# BeagleboneCape.net
KiCad netlist of a schematic drawn in EAGLE
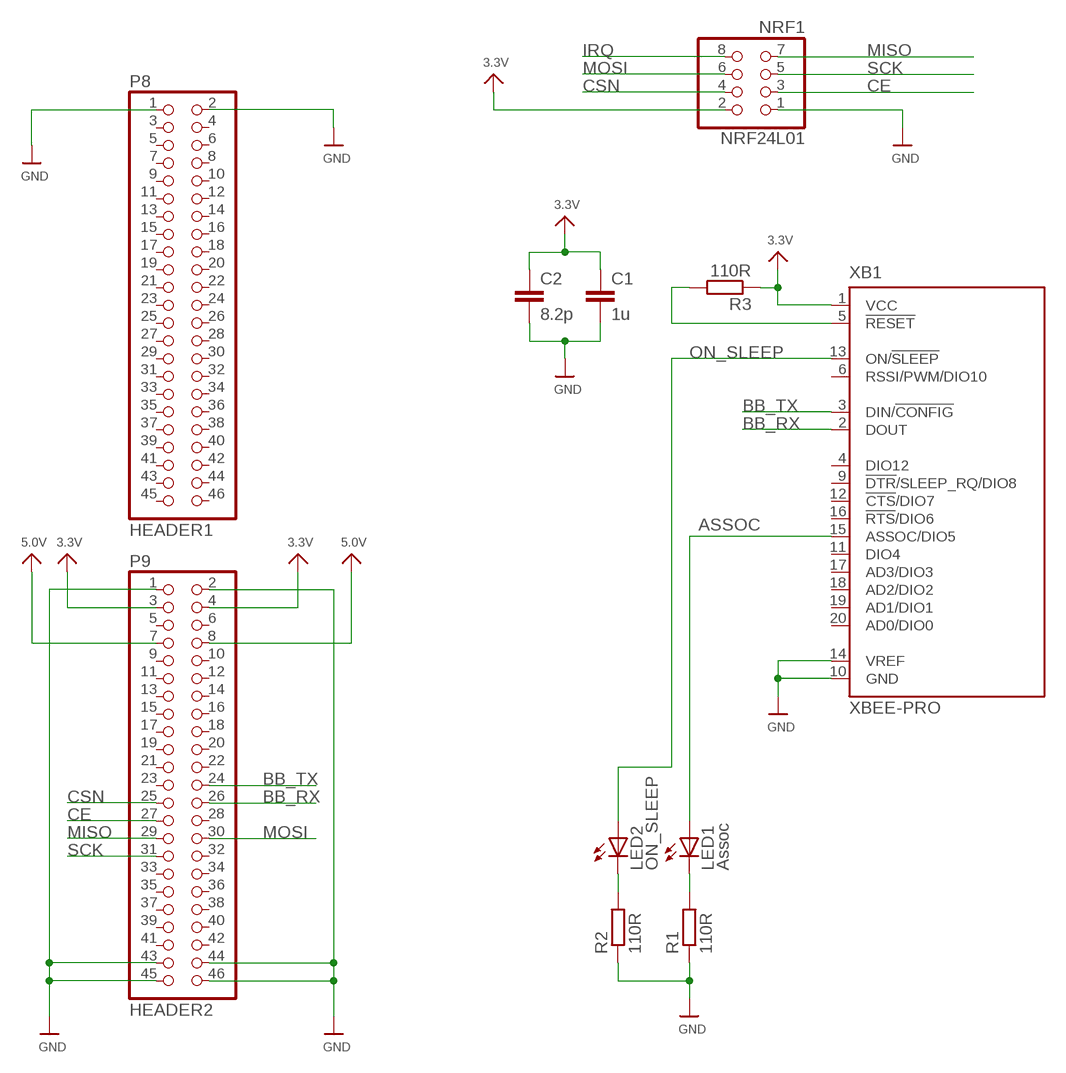
[diagram p0: schematic, sheet 1]

(export (version "E")
  (design (tool "Eeschema 10.0.6"))
  (components
    (comp (ref "C1")
      (value "1u")
      (footprint "eagle-import:C025-025X050")
      (libsource (lib "eagle-import") (part "C-EU025-025X050"))
    )
    (comp (ref "C2")
      (value "8.2p")
      (footprint "eagle-import:C025-025X050")
      (libsource (lib "eagle-import") (part "C-EU025-025X050"))
    )
    (comp (ref "LED1")
      (value "Assoc")
      (footprint "eagle-import:LED5MM")
      (libsource (lib "eagle-import") (part "LED5MM"))
    )
    (comp (ref "LED2")
      (value "ON_SLEEP")
      (footprint "eagle-import:LED5MM")
      (libsource (lib "eagle-import") (part "LED5MM"))
    )
    (comp (ref "NRF24L01")
      (value "NRF1")
      (footprint "eagle-import:2X04")
      (libsource (lib "eagle-import") (part "PINHD-2X4"))
    )
    (comp (ref "P8")
      (value "HEADER1")
      (footprint "eagle-import:2X23")
      (libsource (lib "eagle-import") (part "PINHD-2X24"))
    )
    (comp (ref "P9")
      (value "HEADER2")
      (footprint "eagle-import:2X23")
      (libsource (lib "eagle-import") (part "PINHD-2X24"))
    )
    (comp (ref "R1")
      (value "110R")
      (footprint "eagle-import:0207_7")
      (libsource (lib "eagle-import") (part "R-EU_0207/7"))
    )
    (comp (ref "R2")
      (value "110R")
      (footprint "eagle-import:0207_7")
      (libsource (lib "eagle-import") (part "R-EU_0207/7"))
    )
    (comp (ref "R3")
      (value "110R")
      (footprint "eagle-import:0207_7")
      (libsource (lib "eagle-import") (part "R-EU_0207/7"))
    )
    (comp (ref "XB1")
      (value "XBEE-PRO")
      (footprint "eagle-import:XBEE-PRO")
      (fields (field (name "MPN") "XBP24-AWI-001"))
      (libsource (lib "eagle-import") (part "XBEE-PRO"))
    )
  )
  (nets
    (net (code "1") (name "/ASSOC") (class "Default")
      (node (ref "LED1") (pin "A") (pinfunction "A_A") (pintype "passive"))
      (node (ref "XB1") (pin "15") (pinfunction "ASSOC/DIO5_15") (pintype "bidirectional"))
    )
    (net (code "2") (name "/BB_RX") (class "Default")
      (node (ref "P9") (pin "26") (pinfunction "26_26") (pintype "passive"))
      (node (ref "XB1") (pin "2") (pinfunction "DOUT_2") (pintype "output"))
    )
    (net (code "3") (name "/BB_TX") (class "Default")
      (node (ref "P9") (pin "24") (pinfunction "24_24") (pintype "passive"))
      (node (ref "XB1") (pin "3") (pinfunction "DIN/~{CONFIG}_3") (pintype "input"))
    )
    (net (code "4") (name "/CE") (class "Default")
      (node (ref "NRF24L01") (pin "3") (pinfunction "3_3") (pintype "passive"))
      (node (ref "P9") (pin "27") (pinfunction "27_27") (pintype "passive"))
    )
    (net (code "5") (name "/CSN") (class "Default")
      (node (ref "NRF24L01") (pin "4") (pinfunction "4_4") (pintype "passive"))
      (node (ref "P9") (pin "25") (pinfunction "25_25") (pintype "passive"))
    )
    (net (code "6") (name "/IRQ") (class "Default")
      (node (ref "NRF24L01") (pin "8") (pinfunction "8_8") (pintype "passive"))
    )
    (net (code "7") (name "/MISO") (class "Default")
      (node (ref "NRF24L01") (pin "7") (pinfunction "7_7") (pintype "passive"))
      (node (ref "P9") (pin "29") (pinfunction "29_29") (pintype "passive"))
    )
    (net (code "8") (name "/MOSI") (class "Default")
      (node (ref "NRF24L01") (pin "6") (pinfunction "6_6") (pintype "passive"))
      (node (ref "P9") (pin "30") (pinfunction "30_30") (pintype "passive"))
    )
    (net (code "9") (name "/ON_SLEEP") (class "Default")
      (node (ref "LED2") (pin "A") (pinfunction "A_A") (pintype "passive"))
      (node (ref "XB1") (pin "13") (pinfunction "ON/~{SLEEP}_13") (pintype "output"))
    )
    (net (code "10") (name "/SCK") (class "Default")
      (node (ref "NRF24L01") (pin "5") (pinfunction "5_5") (pintype "passive"))
      (node (ref "P9") (pin "31") (pinfunction "31_31") (pintype "passive"))
    )
    (net (code "11") (name "3.3V") (class "Default")
      (node (ref "C1") (pin "1") (pinfunction "1_1") (pintype "passive"))
      (node (ref "C2") (pin "1") (pinfunction "1_1") (pintype "passive"))
      (node (ref "NRF24L01") (pin "2") (pinfunction "2_2") (pintype "passive"))
      (node (ref "P9") (pin "3") (pinfunction "3_3") (pintype "passive"))
      (node (ref "P9") (pin "4") (pinfunction "4_4") (pintype "passive"))
      (node (ref "R3") (pin "1") (pinfunction "1_1") (pintype "passive"))
      (node (ref "XB1") (pin "1") (pinfunction "VCC_1") (pintype "power_in"))
    )
    (net (code "12") (name "5.0V") (class "Default")
      (node (ref "P9") (pin "7") (pinfunction "7_7") (pintype "passive"))
      (node (ref "P9") (pin "8") (pinfunction "8_8") (pintype "passive"))
    )
    (net (code "13") (name "GND") (class "Default")
      (node (ref "C1") (pin "2") (pinfunction "2_2") (pintype "passive"))
      (node (ref "C2") (pin "2") (pinfunction "2_2") (pintype "passive"))
      (node (ref "NRF24L01") (pin "1") (pinfunction "1_1") (pintype "passive"))
      (node (ref "P8") (pin "1") (pinfunction "1_1") (pintype "passive"))
      (node (ref "P8") (pin "2") (pinfunction "2_2") (pintype "passive"))
      (node (ref "P9") (pin "1") (pinfunction "1_1") (pintype "passive"))
      (node (ref "P9") (pin "2") (pinfunction "2_2") (pintype "passive"))
      (node (ref "P9") (pin "43") (pinfunction "43_43") (pintype "passive"))
      (node (ref "P9") (pin "44") (pinfunction "44_44") (pintype "passive"))
      (node (ref "P9") (pin "45") (pinfunction "45_45") (pintype "passive"))
      (node (ref "P9") (pin "46") (pinfunction "46_46") (pintype "passive"))
      (node (ref "R1") (pin "1") (pinfunction "1_1") (pintype "passive"))
      (node (ref "R2") (pin "1") (pinfunction "1_1") (pintype "passive"))
      (node (ref "XB1") (pin "10") (pinfunction "GND_10") (pintype "power_in"))
      (node (ref "XB1") (pin "14") (pinfunction "VREF_14") (pintype "input"))
    )
    (net (code "14") (name "Net-(LED1-C)") (class "Default")
      (node (ref "LED1") (pin "K") (pinfunction "C_K") (pintype "passive"))
      (node (ref "R1") (pin "2") (pinfunction "2_2") (pintype "passive"))
    )
    (net (code "15") (name "Net-(LED2-C)") (class "Default")
      (node (ref "LED2") (pin "K") (pinfunction "C_K") (pintype "passive"))
      (node (ref "R2") (pin "2") (pinfunction "2_2") (pintype "passive"))
    )
    (net (code "16") (name "Net-(XB1-~{RESET})") (class "Default")
      (node (ref "R3") (pin "2") (pinfunction "2_2") (pintype "passive"))
      (node (ref "XB1") (pin "5") (pinfunction "~{RESET}_5") (pintype "input"))
    )
    (net (code "17") (name "unconnected-(P8-Pad3)") (class "Default")
      (node (ref "P8") (pin "3") (pinfunction "3_3") (pintype "passive"))
    )
    (net (code "18") (name "unconnected-(P8-Pad4)") (class "Default")
      (node (ref "P8") (pin "4") (pinfunction "4_4") (pintype "passive"))
    )
    (net (code "19") (name "unconnected-(P8-Pad5)") (class "Default")
      (node (ref "P8") (pin "5") (pinfunction "5_5") (pintype "passive"))
    )
    (net (code "20") (name "unconnected-(P8-Pad6)") (class "Default")
      (node (ref "P8") (pin "6") (pinfunction "6_6") (pintype "passive"))
    )
    (net (code "21") (name "unconnected-(P8-Pad7)") (class "Default")
      (node (ref "P8") (pin "7") (pinfunction "7_7") (pintype "passive"))
    )
    (net (code "22") (name "unconnected-(P8-Pad8)") (class "Default")
      (node (ref "P8") (pin "8") (pinfunction "8_8") (pintype "passive"))
    )
    (net (code "23") (name "unconnected-(P8-Pad9)") (class "Default")
      (node (ref "P8") (pin "9") (pinfunction "9_9") (pintype "passive"))
    )
    (net (code "24") (name "unconnected-(P8-Pad10)") (class "Default")
      (node (ref "P8") (pin "10") (pinfunction "10_10") (pintype "passive"))
    )
    (net (code "25") (name "unconnected-(P8-Pad11)") (class "Default")
      (node (ref "P8") (pin "11") (pinfunction "11_11") (pintype "passive"))
    )
    (net (code "26") (name "unconnected-(P8-Pad12)") (class "Default")
      (node (ref "P8") (pin "12") (pinfunction "12_12") (pintype "passive"))
    )
    (net (code "27") (name "unconnected-(P8-Pad13)") (class "Default")
      (node (ref "P8") (pin "13") (pinfunction "13_13") (pintype "passive"))
    )
    (net (code "28") (name "unconnected-(P8-Pad14)") (class "Default")
      (node (ref "P8") (pin "14") (pinfunction "14_14") (pintype "passive"))
    )
    (net (code "29") (name "unconnected-(P8-Pad15)") (class "Default")
      (node (ref "P8") (pin "15") (pinfunction "15_15") (pintype "passive"))
    )
    (net (code "30") (name "unconnected-(P8-Pad16)") (class "Default")
      (node (ref "P8") (pin "16") (pinfunction "16_16") (pintype "passive"))
    )
    (net (code "31") (name "unconnected-(P8-Pad17)") (class "Default")
      (node (ref "P8") (pin "17") (pinfunction "17_17") (pintype "passive"))
    )
    (net (code "32") (name "unconnected-(P8-Pad18)") (class "Default")
      (node (ref "P8") (pin "18") (pinfunction "18_18") (pintype "passive"))
    )
    (net (code "33") (name "unconnected-(P8-Pad19)") (class "Default")
      (node (ref "P8") (pin "19") (pinfunction "19_19") (pintype "passive"))
    )
    (net (code "34") (name "unconnected-(P8-Pad20)") (class "Default")
      (node (ref "P8") (pin "20") (pinfunction "20_20") (pintype "passive"))
    )
    (net (code "35") (name "unconnected-(P8-Pad21)") (class "Default")
      (node (ref "P8") (pin "21") (pinfunction "21_21") (pintype "passive"))
    )
    (net (code "36") (name "unconnected-(P8-Pad22)") (class "Default")
      (node (ref "P8") (pin "22") (pinfunction "22_22") (pintype "passive"))
    )
    (net (code "37") (name "unconnected-(P8-Pad23)") (class "Default")
      (node (ref "P8") (pin "23") (pinfunction "23_23") (pintype "passive"))
    )
    (net (code "38") (name "unconnected-(P8-Pad24)") (class "Default")
      (node (ref "P8") (pin "24") (pinfunction "24_24") (pintype "passive"))
    )
    (net (code "39") (name "unconnected-(P8-Pad25)") (class "Default")
      (node (ref "P8") (pin "25") (pinfunction "25_25") (pintype "passive"))
    )
    (net (code "40") (name "unconnected-(P8-Pad26)") (class "Default")
      (node (ref "P8") (pin "26") (pinfunction "26_26") (pintype "passive"))
    )
    (net (code "41") (name "unconnected-(P8-Pad27)") (class "Default")
      (node (ref "P8") (pin "27") (pinfunction "27_27") (pintype "passive"))
    )
    (net (code "42") (name "unconnected-(P8-Pad28)") (class "Default")
      (node (ref "P8") (pin "28") (pinfunction "28_28") (pintype "passive"))
    )
    (net (code "43") (name "unconnected-(P8-Pad29)") (class "Default")
      (node (ref "P8") (pin "29") (pinfunction "29_29") (pintype "passive"))
    )
    (net (code "44") (name "unconnected-(P8-Pad30)") (class "Default")
      (node (ref "P8") (pin "30") (pinfunction "30_30") (pintype "passive"))
    )
    (net (code "45") (name "unconnected-(P8-Pad31)") (class "Default")
      (node (ref "P8") (pin "31") (pinfunction "31_31") (pintype "passive"))
    )
    (net (code "46") (name "unconnected-(P8-Pad32)") (class "Default")
      (node (ref "P8") (pin "32") (pinfunction "32_32") (pintype "passive"))
    )
    (net (code "47") (name "unconnected-(P8-Pad33)") (class "Default")
      (node (ref "P8") (pin "33") (pinfunction "33_33") (pintype "passive"))
    )
    (net (code "48") (name "unconnected-(P8-Pad34)") (class "Default")
      (node (ref "P8") (pin "34") (pinfunction "34_34") (pintype "passive"))
    )
    (net (code "49") (name "unconnected-(P8-Pad35)") (class "Default")
      (node (ref "P8") (pin "35") (pinfunction "35_35") (pintype "passive"))
    )
    (net (code "50") (name "unconnected-(P8-Pad36)") (class "Default")
      (node (ref "P8") (pin "36") (pinfunction "36_36") (pintype "passive"))
    )
    (net (code "51") (name "unconnected-(P8-Pad37)") (class "Default")
      (node (ref "P8") (pin "37") (pinfunction "37_37") (pintype "passive"))
    )
    (net (code "52") (name "unconnected-(P8-Pad38)") (class "Default")
      (node (ref "P8") (pin "38") (pinfunction "38_38") (pintype "passive"))
    )
    (net (code "53") (name "unconnected-(P8-Pad39)") (class "Default")
      (node (ref "P8") (pin "39") (pinfunction "39_39") (pintype "passive"))
    )
    (net (code "54") (name "unconnected-(P8-Pad40)") (class "Default")
      (node (ref "P8") (pin "40") (pinfunction "40_40") (pintype "passive"))
    )
    (net (code "55") (name "unconnected-(P8-Pad41)") (class "Default")
      (node (ref "P8") (pin "41") (pinfunction "41_41") (pintype "passive"))
    )
    (net (code "56") (name "unconnected-(P8-Pad42)") (class "Default")
      (node (ref "P8") (pin "42") (pinfunction "42_42") (pintype "passive"))
    )
    (net (code "57") (name "unconnected-(P8-Pad43)") (class "Default")
      (node (ref "P8") (pin "43") (pinfunction "43_43") (pintype "passive"))
    )
    (net (code "58") (name "unconnected-(P8-Pad44)") (class "Default")
      (node (ref "P8") (pin "44") (pinfunction "44_44") (pintype "passive"))
    )
    (net (code "59") (name "unconnected-(P8-Pad45)") (class "Default")
      (node (ref "P8") (pin "45") (pinfunction "45_45") (pintype "passive"))
    )
    (net (code "60") (name "unconnected-(P8-Pad46)") (class "Default")
      (node (ref "P8") (pin "46") (pinfunction "46_46") (pintype "passive"))
    )
    (net (code "61") (name "unconnected-(P9-Pad5)") (class "Default")
      (node (ref "P9") (pin "5") (pinfunction "5_5") (pintype "passive"))
    )
    (net (code "62") (name "unconnected-(P9-Pad6)") (class "Default")
      (node (ref "P9") (pin "6") (pinfunction "6_6") (pintype "passive"))
    )
    (net (code "63") (name "unconnected-(P9-Pad9)") (class "Default")
      (node (ref "P9") (pin "9") (pinfunction "9_9") (pintype "passive"))
    )
    (net (code "64") (name "unconnected-(P9-Pad10)") (class "Default")
      (node (ref "P9") (pin "10") (pinfunction "10_10") (pintype "passive"))
    )
    (net (code "65") (name "unconnected-(P9-Pad11)") (class "Default")
      (node (ref "P9") (pin "11") (pinfunction "11_11") (pintype "passive"))
    )
    (net (code "66") (name "unconnected-(P9-Pad12)") (class "Default")
      (node (ref "P9") (pin "12") (pinfunction "12_12") (pintype "passive"))
    )
    (net (code "67") (name "unconnected-(P9-Pad13)") (class "Default")
      (node (ref "P9") (pin "13") (pinfunction "13_13") (pintype "passive"))
    )
    (net (code "68") (name "unconnected-(P9-Pad14)") (class "Default")
      (node (ref "P9") (pin "14") (pinfunction "14_14") (pintype "passive"))
    )
    (net (code "69") (name "unconnected-(P9-Pad15)") (class "Default")
      (node (ref "P9") (pin "15") (pinfunction "15_15") (pintype "passive"))
    )
    (net (code "70") (name "unconnected-(P9-Pad16)") (class "Default")
      (node (ref "P9") (pin "16") (pinfunction "16_16") (pintype "passive"))
    )
    (net (code "71") (name "unconnected-(P9-Pad17)") (class "Default")
      (node (ref "P9") (pin "17") (pinfunction "17_17") (pintype "passive"))
    )
    (net (code "72") (name "unconnected-(P9-Pad18)") (class "Default")
      (node (ref "P9") (pin "18") (pinfunction "18_18") (pintype "passive"))
    )
    (net (code "73") (name "unconnected-(P9-Pad19)") (class "Default")
      (node (ref "P9") (pin "19") (pinfunction "19_19") (pintype "passive"))
    )
    (net (code "74") (name "unconnected-(P9-Pad20)") (class "Default")
      (node (ref "P9") (pin "20") (pinfunction "20_20") (pintype "passive"))
    )
    (net (code "75") (name "unconnected-(P9-Pad21)") (class "Default")
      (node (ref "P9") (pin "21") (pinfunction "21_21") (pintype "passive"))
    )
    (net (code "76") (name "unconnected-(P9-Pad22)") (class "Default")
      (node (ref "P9") (pin "22") (pinfunction "22_22") (pintype "passive"))
    )
    (net (code "77") (name "unconnected-(P9-Pad23)") (class "Default")
      (node (ref "P9") (pin "23") (pinfunction "23_23") (pintype "passive"))
    )
    (net (code "78") (name "unconnected-(P9-Pad28)") (class "Default")
      (node (ref "P9") (pin "28") (pinfunction "28_28") (pintype "passive"))
    )
    (net (code "79") (name "unconnected-(P9-Pad32)") (class "Default")
      (node (ref "P9") (pin "32") (pinfunction "32_32") (pintype "passive"))
    )
    (net (code "80") (name "unconnected-(P9-Pad33)") (class "Default")
      (node (ref "P9") (pin "33") (pinfunction "33_33") (pintype "passive"))
    )
    (net (code "81") (name "unconnected-(P9-Pad34)") (class "Default")
      (node (ref "P9") (pin "34") (pinfunction "34_34") (pintype "passive"))
    )
    (net (code "82") (name "unconnected-(P9-Pad35)") (class "Default")
      (node (ref "P9") (pin "35") (pinfunction "35_35") (pintype "passive"))
    )
    (net (code "83") (name "unconnected-(P9-Pad36)") (class "Default")
      (node (ref "P9") (pin "36") (pinfunction "36_36") (pintype "passive"))
    )
    (net (code "84") (name "unconnected-(P9-Pad37)") (class "Default")
      (node (ref "P9") (pin "37") (pinfunction "37_37") (pintype "passive"))
    )
    (net (code "85") (name "unconnected-(P9-Pad38)") (class "Default")
      (node (ref "P9") (pin "38") (pinfunction "38_38") (pintype "passive"))
    )
    (net (code "86") (name "unconnected-(P9-Pad39)") (class "Default")
      (node (ref "P9") (pin "39") (pinfunction "39_39") (pintype "passive"))
    )
    (net (code "87") (name "unconnected-(P9-Pad40)") (class "Default")
      (node (ref "P9") (pin "40") (pinfunction "40_40") (pintype "passive"))
    )
    (net (code "88") (name "unconnected-(P9-Pad41)") (class "Default")
      (node (ref "P9") (pin "41") (pinfunction "41_41") (pintype "passive"))
    )
    (net (code "89") (name "unconnected-(P9-Pad42)") (class "Default")
      (node (ref "P9") (pin "42") (pinfunction "42_42") (pintype "passive"))
    )
    (net (code "90") (name "unconnected-(XB1-AD0{slash}DIO0-Pad20)") (class "Default")
      (node (ref "XB1") (pin "20") (pinfunction "AD0/DIO0_20") (pintype "bidirectional"))
    )
    (net (code "91") (name "unconnected-(XB1-AD1{slash}DIO1-Pad19)") (class "Default")
      (node (ref "XB1") (pin "19") (pinfunction "AD1/DIO1_19") (pintype "bidirectional"))
    )
    (net (code "92") (name "unconnected-(XB1-AD2{slash}DIO2-Pad18)") (class "Default")
      (node (ref "XB1") (pin "18") (pinfunction "AD2/DIO2_18") (pintype "bidirectional"))
    )
    (net (code "93") (name "unconnected-(XB1-AD3{slash}DIO3-Pad17)") (class "Default")
      (node (ref "XB1") (pin "17") (pinfunction "AD3/DIO3_17") (pintype "bidirectional"))
    )
    (net (code "94") (name "unconnected-(XB1-DIO4-Pad11)") (class "Default")
      (node (ref "XB1") (pin "11") (pinfunction "DIO4_11") (pintype "bidirectional"))
    )
    (net (code "95") (name "unconnected-(XB1-DIO12-Pad4)") (class "Default")
      (node (ref "XB1") (pin "4") (pinfunction "DIO12_4") (pintype "bidirectional"))
    )
    (net (code "96") (name "unconnected-(XB1-RSSI{slash}PWM{slash}DIO10-Pad6)") (class "Default")
      (node (ref "XB1") (pin "6") (pinfunction "RSSI/PWM/DIO10_6") (pintype "output"))
    )
    (net (code "97") (name "unconnected-(XB1-~{CTS}{slash}DIO7-Pad12)") (class "Default")
      (node (ref "XB1") (pin "12") (pinfunction "~{CTS}/DIO7_12") (pintype "bidirectional"))
    )
    (net (code "98") (name "unconnected-(XB1-~{DTR}{slash}SLEEP_RQ{slash}DIO8-Pad9)") (class "Default")
      (node (ref "XB1") (pin "9") (pinfunction "~{DTR}/SLEEP_RQ/DIO8_9") (pintype "bidirectional"))
    )
    (net (code "99") (name "unconnected-(XB1-~{RTS}{slash}DIO6-Pad16)") (class "Default")
      (node (ref "XB1") (pin "16") (pinfunction "~{RTS}/DIO6_16") (pintype "bidirectional"))
    )
  )
)
